# irisc.net
KiCad netlist of a schematic drawn in EAGLE
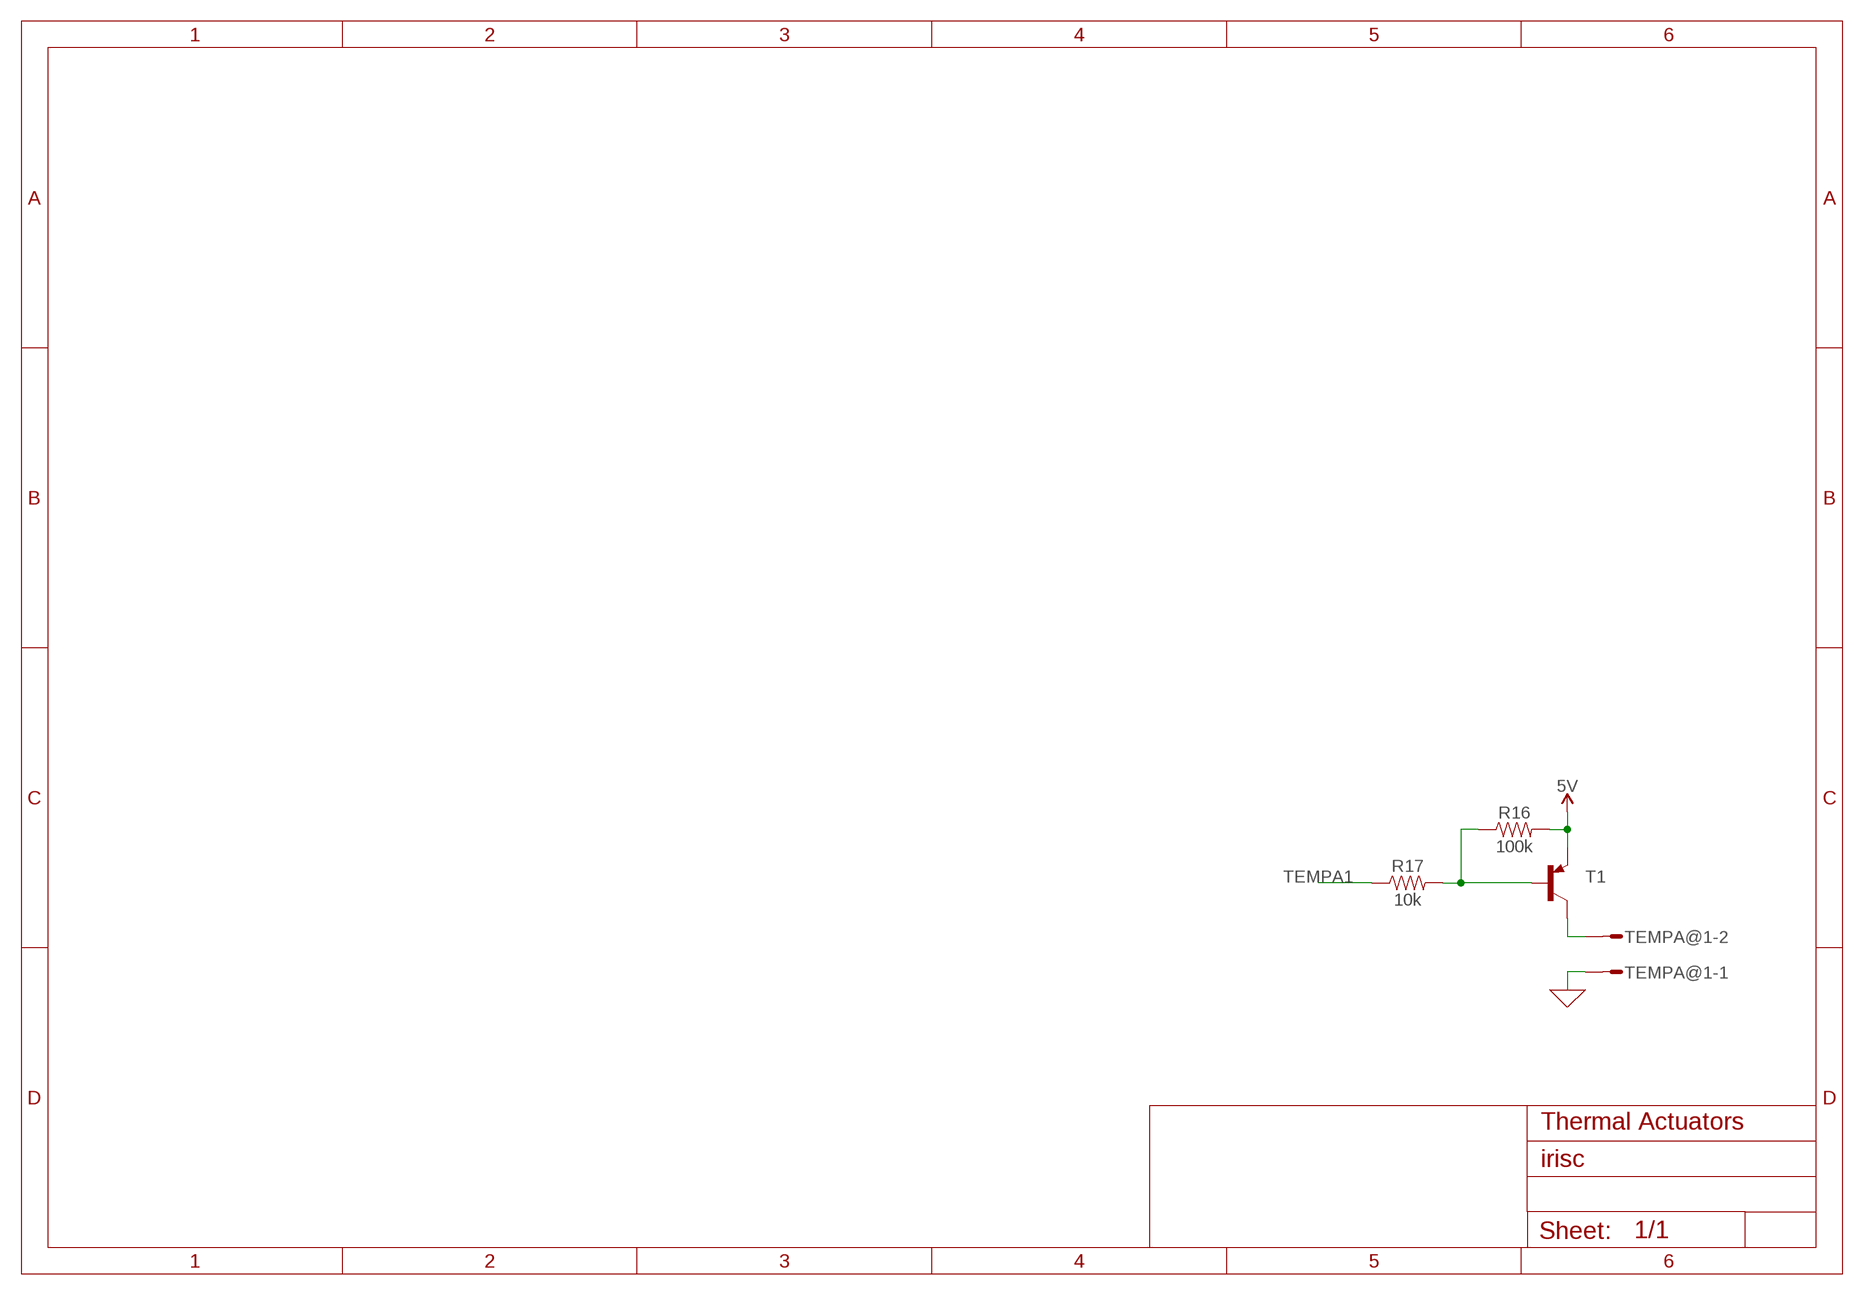
[diagram p0: schematic, sheet 1]

(export (version "E")
  (design (tool "Eeschema 10.0.6"))
  (components
    (comp (ref "R16")
      (value "100k")
      (footprint "eagle-import:0603")
      (libsource (lib "eagle-import") (part "100KOHM-0603-1/10W-1%"))
    )
    (comp (ref "R17")
      (value "10k")
      (footprint "eagle-import:0603")
      (libsource (lib "eagle-import") (part "100KOHM-0603-1/10W-1%"))
    )
    (comp (ref "T1")
      (value "-PNP-SOT23-BEC")
      (footprint "eagle-import:SOT23-BEC")
      (libsource (lib "eagle-import") (part "-PNP-SOT23-BEC"))
    )
    (comp (ref "TEMPA@1")
      (value "L02P")
      (footprint "eagle-import:L02P")
      (libsource (lib "eagle-import") (part "L02P"))
    )
  )
  (nets
    (net (code "1") (name "/TEMPA1") (class "Default")
      (node (ref "R17") (pin "1") (pinfunction "1_1") (pintype "passive"))
    )
    (net (code "2") (name "5V") (class "Default")
      (node (ref "R16") (pin "2") (pinfunction "2_2") (pintype "passive"))
      (node (ref "T1") (pin "E") (pinfunction "E_E") (pintype "passive"))
    )
    (net (code "3") (name "GND") (class "Default")
      (node (ref "TEMPA@1") (pin "1") (pinfunction "S_1") (pintype "passive"))
    )
    (net (code "4") (name "Net-(R16-Pad1)") (class "Default")
      (node (ref "R16") (pin "1") (pinfunction "1_1") (pintype "passive"))
      (node (ref "R17") (pin "2") (pinfunction "2_2") (pintype "passive"))
      (node (ref "T1") (pin "B") (pinfunction "B_B") (pintype "passive"))
    )
    (net (code "5") (name "Net-(TEMPA@1B-S)") (class "Default")
      (node (ref "T1") (pin "C") (pinfunction "C_C") (pintype "passive"))
      (node (ref "TEMPA@1") (pin "2") (pinfunction "S_2") (pintype "passive"))
    )
  )
)
